# lm2596_current_limited_charger.net
KiCad netlist of a schematic drawn in EAGLE
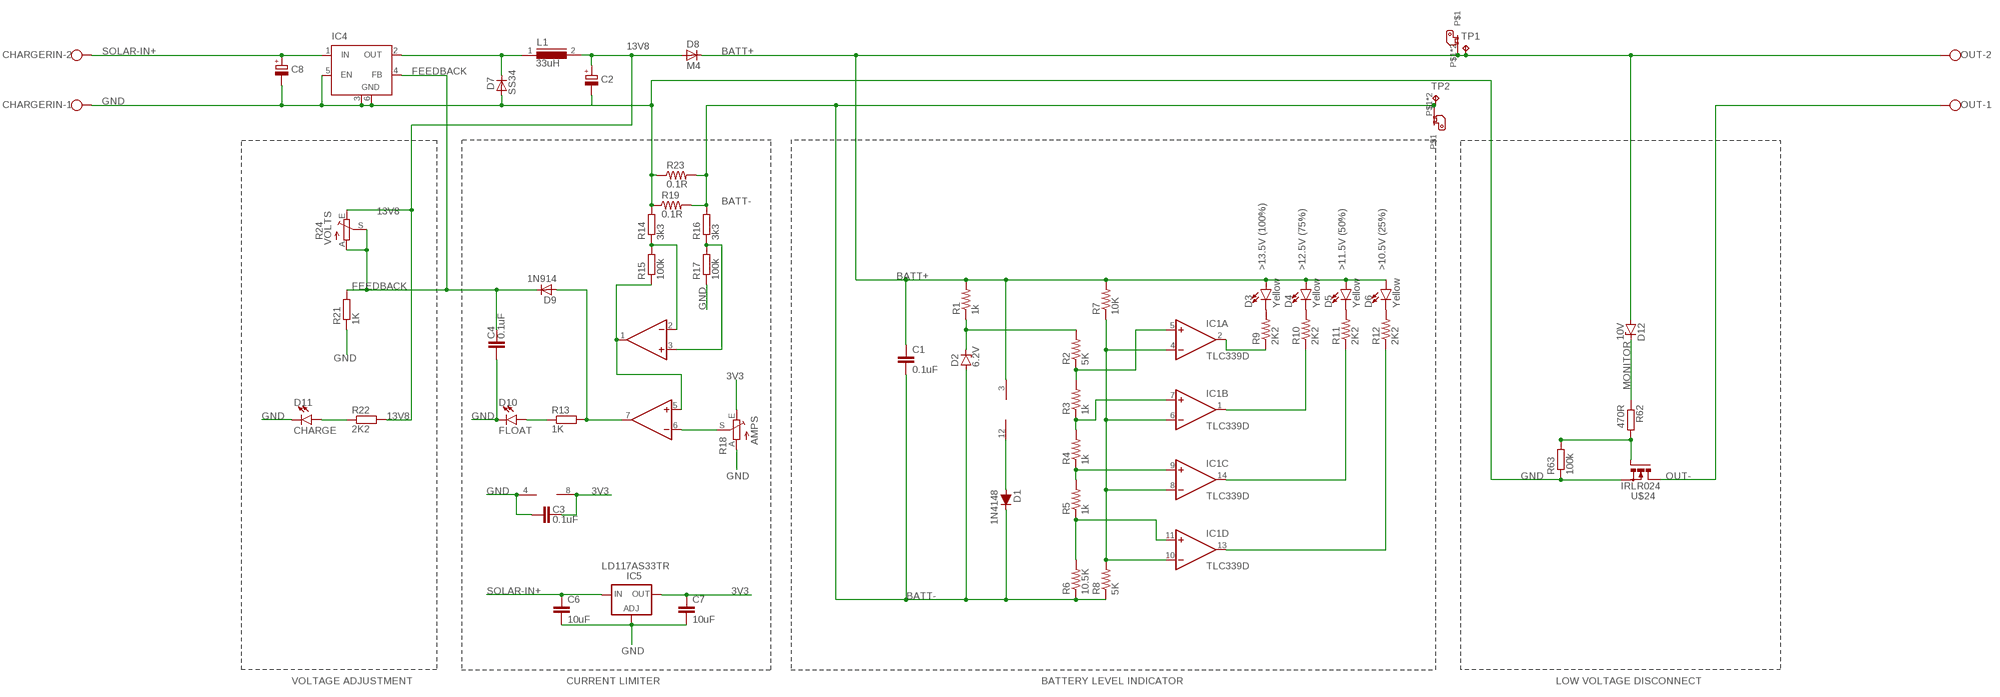
[diagram p0: schematic, sheet 1]

(export (version "E")
  (design (tool "Eeschema 10.0.6"))
  (components
    (comp (ref "C1")
      (value "0.1uF")
      (footprint "eagle-import:C1206K")
      (libsource (lib "eagle-import") (part "C-EUC1206K"))
    )
    (comp (ref "C2")
      (value "CPOL-EUE3.5-8")
      (footprint "eagle-import:E3,5-8")
      (libsource (lib "eagle-import") (part "CPOL-EUE3.5-8"))
    )
    (comp (ref "C3")
      (value "0.1uF")
      (footprint "eagle-import:C1206K")
      (libsource (lib "eagle-import") (part "C-EUC1206K"))
    )
    (comp (ref "C4")
      (value "0.1uF")
      (footprint "eagle-import:C1206K")
      (libsource (lib "eagle-import") (part "C-EUC1206K"))
    )
    (comp (ref "C6")
      (value "10uF")
      (footprint "eagle-import:C1206K")
      (libsource (lib "eagle-import") (part "C-EUC1206K"))
    )
    (comp (ref "C7")
      (value "10uF")
      (footprint "eagle-import:C1206K")
      (libsource (lib "eagle-import") (part "C-EUC1206K"))
    )
    (comp (ref "C8")
      (value "CPOL-EUE3.5-8")
      (footprint "eagle-import:E3,5-8")
      (libsource (lib "eagle-import") (part "CPOL-EUE3.5-8"))
    )
    (comp (ref "CHARGERIN")
      (value "W237-102")
      (footprint "eagle-import:W237-102")
      (fields (field (name "MPN") "237-102"))
      (libsource (lib "eagle-import") (part "W237-102"))
    )
    (comp (ref "D1")
      (value "1N4148")
      (footprint "eagle-import:SOD-323")
      (libsource (lib "eagle-import") (part "DIODE-BAS16J"))
    )
    (comp (ref "D2")
      (value "6.2V")
      (footprint "eagle-import:SMB")
      (libsource (lib "eagle-import") (part "ZENER-DIODESMB"))
    )
    (comp (ref "D3")
      (value "Yellow")
      (footprint "eagle-import:LED-1206")
      (libsource (lib "eagle-import") (part "LED-YELLOWLILYPAD"))
    )
    (comp (ref "D4")
      (value "Yellow")
      (footprint "eagle-import:LED-1206")
      (libsource (lib "eagle-import") (part "LED-YELLOWLILYPAD"))
    )
    (comp (ref "D5")
      (value "Yellow")
      (footprint "eagle-import:LED-1206")
      (libsource (lib "eagle-import") (part "LED-YELLOWLILYPAD"))
    )
    (comp (ref "D6")
      (value "Yellow")
      (footprint "eagle-import:LED-1206")
      (libsource (lib "eagle-import") (part "LED-YELLOWLILYPAD"))
    )
    (comp (ref "D7")
      (value "SS34")
      (footprint "eagle-import:SOD87")
      (libsource (lib "eagle-import") (part "D-SOD-87"))
    )
    (comp (ref "D8")
      (value "M4")
      (footprint "eagle-import:SOD87")
      (libsource (lib "eagle-import") (part "D-SOD-87"))
    )
    (comp (ref "D9")
      (value "1N914")
      (footprint "eagle-import:SOD87")
      (libsource (lib "eagle-import") (part "D-SOD-87"))
    )
    (comp (ref "D10")
      (value "FLOAT")
      (footprint "eagle-import:LED-1206")
      (libsource (lib "eagle-import") (part "LED-YELLOWLILYPAD"))
    )
    (comp (ref "D11")
      (value "CHARGE")
      (footprint "eagle-import:LED-1206")
      (libsource (lib "eagle-import") (part "LED-YELLOWLILYPAD"))
    )
    (comp (ref "D12")
      (value "10V")
      (footprint "eagle-import:SMB")
      (libsource (lib "eagle-import") (part "ZENER-DIODESMB"))
    )
    (comp (ref "IC1")
      (value "TLC339D")
      (footprint "eagle-import:SO14")
      (libsource (lib "eagle-import") (part "TLC339D"))
    )
    (comp (ref "IC2")
      (value "MCP602SN")
      (footprint "eagle-import:SO08")
      (libsource (lib "eagle-import") (part "MCP602SN"))
    )
    (comp (ref "IC4")
      (value "LM2596S")
      (footprint "eagle-import:TO263-5")
      (libsource (lib "eagle-import") (part "LM2596S"))
    )
    (comp (ref "IC5")
      (value "LD117AS33TR")
      (footprint "eagle-import:SOT223")
      (libsource (lib "eagle-import") (part "LD117A?S33TR"))
    )
    (comp (ref "L1")
      (value "33uH")
      (footprint "eagle-import:DR127")
      (libsource (lib "eagle-import") (part "DR127"))
    )
    (comp (ref "OUT")
      (value "W237-102")
      (footprint "eagle-import:W237-102")
      (fields (field (name "MPN") "237-102"))
      (libsource (lib "eagle-import") (part "W237-102"))
    )
    (comp (ref "R1")
      (value "1k")
      (footprint "eagle-import:R1206")
      (libsource (lib "eagle-import") (part "R-US_R1206"))
    )
    (comp (ref "R2")
      (value "5K")
      (footprint "eagle-import:R1206")
      (libsource (lib "eagle-import") (part "R-US_R1206"))
    )
    (comp (ref "R3")
      (value "1k")
      (footprint "eagle-import:R1206")
      (libsource (lib "eagle-import") (part "R-US_R1206"))
    )
    (comp (ref "R4")
      (value "1k")
      (footprint "eagle-import:R1206")
      (libsource (lib "eagle-import") (part "R-US_R1206"))
    )
    (comp (ref "R5")
      (value "1k")
      (footprint "eagle-import:R1206")
      (libsource (lib "eagle-import") (part "R-US_R1206"))
    )
    (comp (ref "R6")
      (value "10.5K")
      (footprint "eagle-import:R1206")
      (libsource (lib "eagle-import") (part "R-US_R1206"))
    )
    (comp (ref "R7")
      (value "10K")
      (footprint "eagle-import:R1206")
      (libsource (lib "eagle-import") (part "R-US_R1206"))
    )
    (comp (ref "R8")
      (value "5K")
      (footprint "eagle-import:R1206")
      (libsource (lib "eagle-import") (part "R-US_R1206"))
    )
    (comp (ref "R9")
      (value "2K2")
      (footprint "eagle-import:R1206")
      (libsource (lib "eagle-import") (part "R-US_R1206"))
    )
    (comp (ref "R10")
      (value "2K2")
      (footprint "eagle-import:R1206")
      (libsource (lib "eagle-import") (part "R-US_R1206"))
    )
    (comp (ref "R11")
      (value "2K2")
      (footprint "eagle-import:R1206")
      (libsource (lib "eagle-import") (part "R-US_R1206"))
    )
    (comp (ref "R12")
      (value "2K2")
      (footprint "eagle-import:R1206")
      (libsource (lib "eagle-import") (part "R-US_R1206"))
    )
    (comp (ref "R13")
      (value "1K")
      (footprint "eagle-import:R1206")
      (libsource (lib "eagle-import") (part "R-EU_R1206"))
    )
    (comp (ref "R14")
      (value "3k3")
      (footprint "eagle-import:R1206")
      (libsource (lib "eagle-import") (part "R-EU_R1206"))
    )
    (comp (ref "R15")
      (value "100k")
      (footprint "eagle-import:R1206")
      (libsource (lib "eagle-import") (part "R-EU_R1206"))
    )
    (comp (ref "R16")
      (value "3k3")
      (footprint "eagle-import:R1206")
      (libsource (lib "eagle-import") (part "R-EU_R1206"))
    )
    (comp (ref "R17")
      (value "100k")
      (footprint "eagle-import:R1206")
      (libsource (lib "eagle-import") (part "R-EU_R1206"))
    )
    (comp (ref "R18")
      (value "AMPS")
      (footprint "eagle-import:B64Y")
      (libsource (lib "eagle-import") (part "TRIM_EU-B64Y"))
    )
    (comp (ref "R19")
      (value "0.1R")
      (footprint "eagle-import:R2512")
      (libsource (lib "eagle-import") (part "R-US_R2512"))
    )
    (comp (ref "R21")
      (value "1K")
      (footprint "eagle-import:R1206")
      (libsource (lib "eagle-import") (part "R-EU_R1206"))
    )
    (comp (ref "R22")
      (value "2K2")
      (footprint "eagle-import:R1206")
      (libsource (lib "eagle-import") (part "R-EU_R1206"))
    )
    (comp (ref "R23")
      (value "0.1R")
      (footprint "eagle-import:R2512")
      (libsource (lib "eagle-import") (part "R-US_R2512"))
    )
    (comp (ref "R24")
      (value "VOLTS")
      (footprint "eagle-import:B64Y")
      (libsource (lib "eagle-import") (part "TRIM_EU-B64Y"))
    )
    (comp (ref "R62")
      (value "470R")
      (footprint "eagle-import:R0603")
      (libsource (lib "eagle-import") (part "resistor_R-EU_R0603"))
    )
    (comp (ref "R63")
      (value "100k")
      (footprint "eagle-import:R0603")
      (libsource (lib "eagle-import") (part "resistor_R-EU_R0603"))
    )
    (comp (ref "TP1")
      (value "TPPAD1-20Y")
      (footprint "eagle-import:P1-20Y")
      (libsource (lib "eagle-import") (part "TPPAD1-20Y"))
    )
    (comp (ref "TP2")
      (value "TPPAD1-20Y")
      (footprint "eagle-import:P1-20Y")
      (libsource (lib "eagle-import") (part "TPPAD1-20Y"))
    )
    (comp (ref "U$2")
      (value "PCB-6.35MM-RA-SPADE")
      (footprint "eagle-import:PCB-6.35MM-RA-SPADE")
      (libsource (lib "eagle-import") (part "PCB-6.35MM-RA-SPADE"))
    )
    (comp (ref "U$3")
      (value "PCB-6.35MM-RA-SPADE")
      (footprint "eagle-import:PCB-6.35MM-RA-SPADE")
      (libsource (lib "eagle-import") (part "PCB-6.35MM-RA-SPADE"))
    )
    (comp (ref "U$24")
      (value "IRLR024")
      (footprint "eagle-import:D-PAK_TO252AA")
      (libsource (lib "eagle-import") (part "N-POWER-MOSFETDPAK-MOSFET"))
    )
  )
  (nets
    (net (code "1") (name "/3V3") (class "Default")
      (node (ref "C3") (pin "2") (pinfunction "2_2") (pintype "passive"))
      (node (ref "C7") (pin "1") (pinfunction "1_1") (pintype "passive"))
      (node (ref "IC2") (pin "8") (pinfunction "V+_8") (pintype "power_in"))
      (node (ref "IC5") (pin "4") (pinfunction "OUT_4") (pintype "passive"))
      (node (ref "R18") (pin "E") (pinfunction "E_E") (pintype "passive"))
    )
    (net (code "2") (name "/13V8") (class "Default")
      (node (ref "C2") (pin "+") (pinfunction "+_+") (pintype "passive"))
      (node (ref "D8") (pin "2") (pinfunction "A_2") (pintype "passive"))
      (node (ref "L1") (pin "2") (pinfunction "2_2") (pintype "passive"))
      (node (ref "R22") (pin "2") (pinfunction "2_2") (pintype "passive"))
      (node (ref "R24") (pin "E") (pinfunction "E_E") (pintype "passive"))
    )
    (net (code "3") (name "/BATT+") (class "Default")
      (node (ref "C1") (pin "1") (pinfunction "1_1") (pintype "passive"))
      (node (ref "D12") (pin "A") (pinfunction "A_A") (pintype "passive"))
      (node (ref "D3") (pin "A") (pinfunction "A_A") (pintype "passive"))
      (node (ref "D4") (pin "A") (pinfunction "A_A") (pintype "passive"))
      (node (ref "D5") (pin "A") (pinfunction "A_A") (pintype "passive"))
      (node (ref "D6") (pin "A") (pinfunction "A_A") (pintype "passive"))
      (node (ref "D8") (pin "1") (pinfunction "C_1") (pintype "passive"))
      (node (ref "IC1") (pin "3") (pinfunction "V+_3") (pintype "power_in"))
      (node (ref "OUT") (pin "2") (pinfunction "KL_2") (pintype "passive"))
      (node (ref "R1") (pin "2") (pinfunction "2_2") (pintype "passive"))
      (node (ref "R7") (pin "2") (pinfunction "2_2") (pintype "passive"))
      (node (ref "TP1") (pin "TP") (pinfunction "TP_TP") (pintype "input"))
      (node (ref "U$2") (pin "P$1") (pinfunction "P$1_P$1") (pintype "bidirectional"))
      (node (ref "U$2") (pin "P$2") (pinfunction "P$1_P$2") (pintype "bidirectional"))
    )
    (net (code "4") (name "/BATT-") (class "Default")
      (node (ref "C1") (pin "2") (pinfunction "2_2") (pintype "passive"))
      (node (ref "D1") (pin "C") (pinfunction "C_C") (pintype "passive"))
      (node (ref "D2") (pin "A") (pinfunction "A_A") (pintype "passive"))
      (node (ref "R16") (pin "2") (pinfunction "2_2") (pintype "passive"))
      (node (ref "R19") (pin "2") (pinfunction "2_2") (pintype "passive"))
      (node (ref "R23") (pin "2") (pinfunction "2_2") (pintype "passive"))
      (node (ref "R6") (pin "1") (pinfunction "1_1") (pintype "passive"))
      (node (ref "R8") (pin "1") (pinfunction "1_1") (pintype "passive"))
      (node (ref "TP2") (pin "TP") (pinfunction "TP_TP") (pintype "input"))
      (node (ref "U$3") (pin "P$1") (pinfunction "P$1_P$1") (pintype "bidirectional"))
      (node (ref "U$3") (pin "P$2") (pinfunction "P$1_P$2") (pintype "bidirectional"))
    )
    (net (code "5") (name "/FEEDBACK") (class "Default")
      (node (ref "C4") (pin "2") (pinfunction "2_2") (pintype "passive"))
      (node (ref "D9") (pin "1") (pinfunction "C_1") (pintype "passive"))
      (node (ref "IC4") (pin "4") (pinfunction "FB_4") (pintype "input"))
      (node (ref "R21") (pin "2") (pinfunction "2_2") (pintype "passive"))
      (node (ref "R24") (pin "A") (pinfunction "A_A") (pintype "passive"))
      (node (ref "R24") (pin "S") (pinfunction "S_S") (pintype "passive"))
    )
    (net (code "6") (name "/GND") (class "Default")
      (node (ref "C2") (pin "-") (pinfunction "-_-") (pintype "passive"))
      (node (ref "C3") (pin "1") (pinfunction "1_1") (pintype "passive"))
      (node (ref "C4") (pin "1") (pinfunction "1_1") (pintype "passive"))
      (node (ref "C6") (pin "2") (pinfunction "2_2") (pintype "passive"))
      (node (ref "C7") (pin "2") (pinfunction "2_2") (pintype "passive"))
      (node (ref "C8") (pin "-") (pinfunction "-_-") (pintype "passive"))
      (node (ref "CHARGERIN") (pin "1") (pinfunction "KL_1") (pintype "passive"))
      (node (ref "D10") (pin "C") (pinfunction "C_C") (pintype "passive"))
      (node (ref "D11") (pin "C") (pinfunction "C_C") (pintype "passive"))
      (node (ref "D7") (pin "2") (pinfunction "A_2") (pintype "passive"))
      (node (ref "IC2") (pin "4") (pinfunction "V-_4") (pintype "power_in"))
      (node (ref "IC4") (pin "3") (pinfunction "GND_3") (pintype "power_in"))
      (node (ref "IC4") (pin "5") (pinfunction "EN_5") (pintype "input"))
      (node (ref "IC4") (pin "6") (pinfunction "GND_6") (pintype "power_in"))
      (node (ref "IC5") (pin "1") (pinfunction "ADJ_1") (pintype "input"))
      (node (ref "R14") (pin "2") (pinfunction "2_2") (pintype "passive"))
      (node (ref "R17") (pin "1") (pinfunction "1_1") (pintype "passive"))
      (node (ref "R18") (pin "A") (pinfunction "A_A") (pintype "passive"))
      (node (ref "R19") (pin "1") (pinfunction "1_1") (pintype "passive"))
      (node (ref "R21") (pin "1") (pinfunction "1_1") (pintype "passive"))
      (node (ref "R23") (pin "1") (pinfunction "1_1") (pintype "passive"))
      (node (ref "R63") (pin "1") (pinfunction "1_1") (pintype "passive"))
      (node (ref "U$24") (pin "3") (pinfunction "S_3") (pintype "passive"))
    )
    (net (code "7") (name "/MONITOR") (class "Default")
      (node (ref "D12") (pin "C") (pinfunction "C_C") (pintype "passive"))
      (node (ref "R62") (pin "1") (pinfunction "1_1") (pintype "passive"))
    )
    (net (code "8") (name "/OUT-") (class "Default")
      (node (ref "OUT") (pin "1") (pinfunction "KL_1") (pintype "passive"))
      (node (ref "U$24") (pin "4") (pinfunction "D_4") (pintype "passive"))
    )
    (net (code "9") (name "/SOLAR-IN+") (class "Default")
      (node (ref "C6") (pin "1") (pinfunction "1_1") (pintype "passive"))
      (node (ref "C8") (pin "+") (pinfunction "+_+") (pintype "passive"))
      (node (ref "CHARGERIN") (pin "2") (pinfunction "KL_2") (pintype "passive"))
      (node (ref "IC4") (pin "1") (pinfunction "IN_1") (pintype "input"))
      (node (ref "IC5") (pin "3") (pinfunction "IN_3") (pintype "input"))
    )
    (net (code "10") (name "Net-(D2-PadC)") (class "Default")
      (node (ref "D2") (pin "C") (pinfunction "C_C") (pintype "passive"))
      (node (ref "R1") (pin "1") (pinfunction "1_1") (pintype "passive"))
      (node (ref "R2") (pin "2") (pinfunction "2_2") (pintype "passive"))
    )
    (net (code "11") (name "Net-(D3-PadC)") (class "Default")
      (node (ref "D3") (pin "C") (pinfunction "C_C") (pintype "passive"))
      (node (ref "R9") (pin "2") (pinfunction "2_2") (pintype "passive"))
    )
    (net (code "12") (name "Net-(D4-PadC)") (class "Default")
      (node (ref "D4") (pin "C") (pinfunction "C_C") (pintype "passive"))
      (node (ref "R10") (pin "2") (pinfunction "2_2") (pintype "passive"))
    )
    (net (code "13") (name "Net-(D5-PadC)") (class "Default")
      (node (ref "D5") (pin "C") (pinfunction "C_C") (pintype "passive"))
      (node (ref "R11") (pin "2") (pinfunction "2_2") (pintype "passive"))
    )
    (net (code "14") (name "Net-(D6-PadC)") (class "Default")
      (node (ref "D6") (pin "C") (pinfunction "C_C") (pintype "passive"))
      (node (ref "R12") (pin "2") (pinfunction "2_2") (pintype "passive"))
    )
    (net (code "15") (name "Net-(D7-C)") (class "Default")
      (node (ref "D7") (pin "1") (pinfunction "C_1") (pintype "passive"))
      (node (ref "IC4") (pin "2") (pinfunction "OUT_2") (pintype "output"))
      (node (ref "L1") (pin "1") (pinfunction "1_1") (pintype "passive"))
    )
    (net (code "16") (name "Net-(D9-A)") (class "Default")
      (node (ref "D9") (pin "2") (pinfunction "A_2") (pintype "passive"))
      (node (ref "IC2") (pin "7") (pinfunction "OUT_7") (pintype "output"))
      (node (ref "R13") (pin "2") (pinfunction "2_2") (pintype "passive"))
    )
    (net (code "17") (name "Net-(D10-PadA)") (class "Default")
      (node (ref "D10") (pin "A") (pinfunction "A_A") (pintype "passive"))
      (node (ref "R13") (pin "1") (pinfunction "1_1") (pintype "passive"))
    )
    (net (code "18") (name "Net-(D11-PadA)") (class "Default")
      (node (ref "D11") (pin "A") (pinfunction "A_A") (pintype "passive"))
      (node (ref "R22") (pin "1") (pinfunction "1_1") (pintype "passive"))
    )
    (net (code "19") (name "Net-(IC1A-+IN)") (class "Default")
      (node (ref "IC1") (pin "5") (pinfunction "+IN_5") (pintype "input"))
      (node (ref "R2") (pin "1") (pinfunction "1_1") (pintype "passive"))
      (node (ref "R3") (pin "2") (pinfunction "2_2") (pintype "passive"))
    )
    (net (code "20") (name "Net-(IC1A--IN)") (class "Default")
      (node (ref "IC1") (pin "10") (pinfunction "-IN_10") (pintype "input"))
      (node (ref "IC1") (pin "4") (pinfunction "-IN_4") (pintype "input"))
      (node (ref "IC1") (pin "6") (pinfunction "-IN_6") (pintype "input"))
      (node (ref "IC1") (pin "8") (pinfunction "-IN_8") (pintype "input"))
      (node (ref "R7") (pin "1") (pinfunction "1_1") (pintype "passive"))
      (node (ref "R8") (pin "2") (pinfunction "2_2") (pintype "passive"))
    )
    (net (code "21") (name "Net-(IC1A-OUT)") (class "Default")
      (node (ref "IC1") (pin "2") (pinfunction "OUT_2") (pintype "output"))
      (node (ref "R9") (pin "1") (pinfunction "1_1") (pintype "passive"))
    )
    (net (code "22") (name "Net-(IC1B-+IN)") (class "Default")
      (node (ref "IC1") (pin "7") (pinfunction "+IN_7") (pintype "input"))
      (node (ref "R3") (pin "1") (pinfunction "1_1") (pintype "passive"))
      (node (ref "R4") (pin "2") (pinfunction "2_2") (pintype "passive"))
    )
    (net (code "23") (name "Net-(IC1B-OUT)") (class "Default")
      (node (ref "IC1") (pin "1") (pinfunction "OUT_1") (pintype "output"))
      (node (ref "R10") (pin "1") (pinfunction "1_1") (pintype "passive"))
    )
    (net (code "24") (name "Net-(IC1C-+IN)") (class "Default")
      (node (ref "IC1") (pin "9") (pinfunction "+IN_9") (pintype "input"))
      (node (ref "R4") (pin "1") (pinfunction "1_1") (pintype "passive"))
      (node (ref "R5") (pin "2") (pinfunction "2_2") (pintype "passive"))
    )
    (net (code "25") (name "Net-(IC1C-OUT)") (class "Default")
      (node (ref "IC1") (pin "14") (pinfunction "OUT_14") (pintype "output"))
      (node (ref "R11") (pin "1") (pinfunction "1_1") (pintype "passive"))
    )
    (net (code "26") (name "Net-(IC1D-+IN)") (class "Default")
      (node (ref "IC1") (pin "11") (pinfunction "+IN_11") (pintype "input"))
      (node (ref "R5") (pin "1") (pinfunction "1_1") (pintype "passive"))
      (node (ref "R6") (pin "2") (pinfunction "2_2") (pintype "passive"))
    )
    (net (code "27") (name "Net-(IC1D-OUT)") (class "Default")
      (node (ref "IC1") (pin "13") (pinfunction "OUT_13") (pintype "output"))
      (node (ref "R12") (pin "1") (pinfunction "1_1") (pintype "passive"))
    )
    (net (code "28") (name "Net-(IC1E-V-)") (class "Default")
      (node (ref "D1") (pin "A") (pinfunction "A_A") (pintype "passive"))
      (node (ref "IC1") (pin "12") (pinfunction "V-_12") (pintype "power_in"))
    )
    (net (code "29") (name "Net-(IC2A-+IN)") (class "Default")
      (node (ref "IC2") (pin "3") (pinfunction "+IN_3") (pintype "input"))
      (node (ref "R16") (pin "1") (pinfunction "1_1") (pintype "passive"))
      (node (ref "R17") (pin "2") (pinfunction "2_2") (pintype "passive"))
    )
    (net (code "30") (name "Net-(IC2A--IN)") (class "Default")
      (node (ref "IC2") (pin "2") (pinfunction "-IN_2") (pintype "input"))
      (node (ref "R14") (pin "1") (pinfunction "1_1") (pintype "passive"))
      (node (ref "R15") (pin "2") (pinfunction "2_2") (pintype "passive"))
    )
    (net (code "31") (name "Net-(IC2A-OUT)") (class "Default")
      (node (ref "IC2") (pin "1") (pinfunction "OUT_1") (pintype "output"))
      (node (ref "IC2") (pin "5") (pinfunction "+IN_5") (pintype "input"))
      (node (ref "R15") (pin "1") (pinfunction "1_1") (pintype "passive"))
    )
    (net (code "32") (name "Net-(IC2B--IN)") (class "Default")
      (node (ref "IC2") (pin "6") (pinfunction "-IN_6") (pintype "input"))
      (node (ref "R18") (pin "S") (pinfunction "S_S") (pintype "passive"))
    )
    (net (code "33") (name "Net-(U$24-G)") (class "Default")
      (node (ref "R62") (pin "2") (pinfunction "2_2") (pintype "passive"))
      (node (ref "R63") (pin "2") (pinfunction "2_2") (pintype "passive"))
      (node (ref "U$24") (pin "1") (pinfunction "G_1") (pintype "passive"))
    )
  )
)
